# head-board.net
KiCad netlist of a schematic drawn in EAGLE
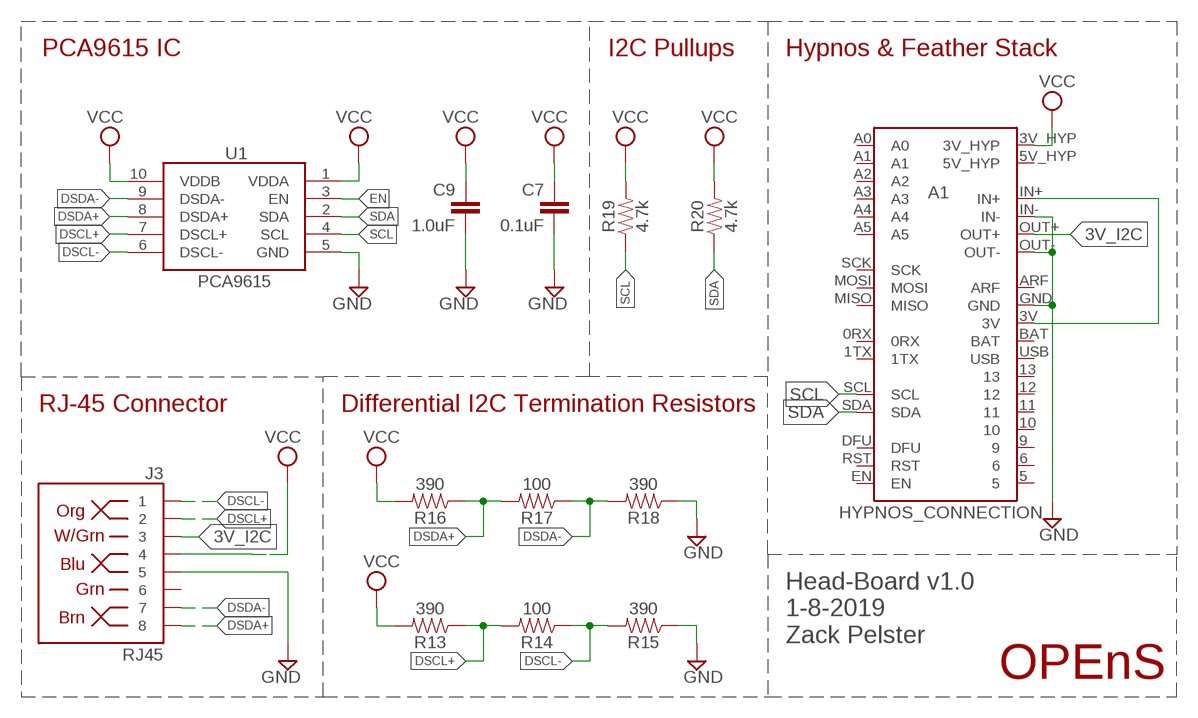
[diagram p0: schematic, sheet 1]

(export (version "E")
  (design (tool "Eeschema 10.0.6"))
  (components
    (comp (ref "A1")
      (value "HYPNOS_CONNECTION")
      (footprint "eagle-import:HYPNOS_CONNECTION")
      (libsource (lib "eagle-import") (part "HYPNOS_CONNECTION"))
    )
    (comp (ref "C7")
      (value "0.1uF")
      (footprint "eagle-import:0603")
      (libsource (lib "eagle-import") (part "0.1UF-0603-25V-(+80/-20%)"))
    )
    (comp (ref "C9")
      (value "1.0uF")
      (footprint "eagle-import:0603")
      (libsource (lib "eagle-import") (part "1.0UF-0603-16V-10%"))
    )
    (comp (ref "J3")
      (value "RJ45")
      (footprint "eagle-import:RJ45-8")
      (libsource (lib "eagle-import") (part "RJ45-8"))
    )
    (comp (ref "R13")
      (value "390")
      (footprint "eagle-import:0603")
      (libsource (lib "eagle-import") (part "390OHM-0603-1/10W-1%"))
    )
    (comp (ref "R14")
      (value "100")
      (footprint "eagle-import:0603")
      (libsource (lib "eagle-import") (part "100OHM-0603-1/10W-1%"))
    )
    (comp (ref "R15")
      (value "390")
      (footprint "eagle-import:0603")
      (libsource (lib "eagle-import") (part "390OHM-0603-1/10W-1%"))
    )
    (comp (ref "R16")
      (value "390")
      (footprint "eagle-import:0603")
      (libsource (lib "eagle-import") (part "390OHM-0603-1/10W-1%"))
    )
    (comp (ref "R17")
      (value "100")
      (footprint "eagle-import:0603")
      (libsource (lib "eagle-import") (part "100OHM-0603-1/10W-1%"))
    )
    (comp (ref "R18")
      (value "390")
      (footprint "eagle-import:0603")
      (libsource (lib "eagle-import") (part "390OHM-0603-1/10W-1%"))
    )
    (comp (ref "R19")
      (value "4.7k")
      (footprint "eagle-import:0603")
      (libsource (lib "eagle-import") (part "4.7KOHM-0603-1/10W-1%"))
    )
    (comp (ref "R20")
      (value "4.7k")
      (footprint "eagle-import:0603")
      (libsource (lib "eagle-import") (part "4.7KOHM-0603-1/10W-1%"))
    )
    (comp (ref "U$1")
      (value "OPENS-LOGO")
      (footprint "eagle-import:OPENS-LOGO")
      (libsource (lib "eagle-import") (part "OPENS-LOGO"))
    )
    (comp (ref "U1")
      (value "PCA9615")
      (footprint "eagle-import:TSSOP10")
      (libsource (lib "eagle-import") (part "PCA9615"))
    )
  )
  (nets
    (net (code "1") (name "/BAT") (class "Default")
      (node (ref "A1") (pin "BAT") (pinfunction "BAT_BAT") (pintype "power_in"))
    )
    (net (code "2") (name "/USB") (class "Default")
      (node (ref "A1") (pin "USB") (pinfunction "USB_USB") (pintype "power_in"))
    )
    (net (code "3") (name "3V_I2C") (class "Default")
      (node (ref "A1") (pin "OUT+") (pinfunction "OUT+_OUT+") (pintype "bidirectional"))
      (node (ref "J3") (pin "3") (pinfunction "3_3") (pintype "bidirectional"))
    )
    (net (code "4") (name "DSCL+") (class "Default")
      (node (ref "J3") (pin "2") (pinfunction "2_2") (pintype "bidirectional"))
      (node (ref "R13") (pin "1") (pinfunction "1_1") (pintype "passive"))
      (node (ref "R14") (pin "2") (pinfunction "2_2") (pintype "passive"))
      (node (ref "U1") (pin "7") (pinfunction "DSCL+_7") (pintype "bidirectional"))
    )
    (net (code "5") (name "DSCL-") (class "Default")
      (node (ref "J3") (pin "1") (pinfunction "1_1") (pintype "bidirectional"))
      (node (ref "R14") (pin "1") (pinfunction "1_1") (pintype "passive"))
      (node (ref "R15") (pin "2") (pinfunction "2_2") (pintype "passive"))
      (node (ref "U1") (pin "6") (pinfunction "DSCL-_6") (pintype "bidirectional"))
    )
    (net (code "6") (name "DSDA+") (class "Default")
      (node (ref "J3") (pin "8") (pinfunction "8_8") (pintype "bidirectional"))
      (node (ref "R16") (pin "1") (pinfunction "1_1") (pintype "passive"))
      (node (ref "R17") (pin "2") (pinfunction "2_2") (pintype "passive"))
      (node (ref "U1") (pin "8") (pinfunction "DSDA+_8") (pintype "bidirectional"))
    )
    (net (code "7") (name "DSDA-") (class "Default")
      (node (ref "J3") (pin "7") (pinfunction "7_7") (pintype "bidirectional"))
      (node (ref "R17") (pin "1") (pinfunction "1_1") (pintype "passive"))
      (node (ref "R18") (pin "2") (pinfunction "2_2") (pintype "passive"))
      (node (ref "U1") (pin "9") (pinfunction "DSDA-_9") (pintype "bidirectional"))
    )
    (net (code "8") (name "EN") (class "Default")
      (node (ref "U1") (pin "3") (pinfunction "EN_3") (pintype "bidirectional"))
    )
    (net (code "9") (name "GND") (class "Default")
      (node (ref "A1") (pin "GND") (pinfunction "GND_GND") (pintype "power_in"))
      (node (ref "A1") (pin "IN-") (pinfunction "IN-_IN-") (pintype "bidirectional"))
      (node (ref "A1") (pin "OUT-") (pinfunction "OUT-_OUT-") (pintype "bidirectional"))
      (node (ref "C7") (pin "2") (pinfunction "2_2") (pintype "passive"))
      (node (ref "C9") (pin "2") (pinfunction "2_2") (pintype "passive"))
      (node (ref "J3") (pin "5") (pinfunction "5_5") (pintype "bidirectional"))
      (node (ref "R15") (pin "1") (pinfunction "1_1") (pintype "passive"))
      (node (ref "R18") (pin "1") (pinfunction "1_1") (pintype "passive"))
      (node (ref "U1") (pin "5") (pinfunction "GND_5") (pintype "bidirectional"))
    )
    (net (code "10") (name "Net-(A1-Pad3V)") (class "Default")
      (node (ref "A1") (pin "3V") (pinfunction "3V_3V") (pintype "power_in"))
      (node (ref "A1") (pin "IN+") (pinfunction "IN+_IN+") (pintype "bidirectional"))
    )
    (net (code "11") (name "SCL") (class "Default")
      (node (ref "A1") (pin "SCL") (pinfunction "SCL_SCL") (pintype "bidirectional"))
      (node (ref "R19") (pin "1") (pinfunction "1_1") (pintype "passive"))
      (node (ref "U1") (pin "4") (pinfunction "SCL_4") (pintype "bidirectional"))
    )
    (net (code "12") (name "SDA") (class "Default")
      (node (ref "A1") (pin "SDA") (pinfunction "SDA_SDA") (pintype "bidirectional"))
      (node (ref "R20") (pin "1") (pinfunction "1_1") (pintype "passive"))
      (node (ref "U1") (pin "2") (pinfunction "SDA_2") (pintype "bidirectional"))
    )
    (net (code "13") (name "VCC") (class "Default")
      (node (ref "A1") (pin "3V_HYP") (pinfunction "3V_HYP_3V_HYP") (pintype "bidirectional"))
      (node (ref "C7") (pin "1") (pinfunction "1_1") (pintype "passive"))
      (node (ref "C9") (pin "1") (pinfunction "1_1") (pintype "passive"))
      (node (ref "J3") (pin "4") (pinfunction "4_4") (pintype "bidirectional"))
      (node (ref "R13") (pin "2") (pinfunction "2_2") (pintype "passive"))
      (node (ref "R16") (pin "2") (pinfunction "2_2") (pintype "passive"))
      (node (ref "R19") (pin "2") (pinfunction "2_2") (pintype "passive"))
      (node (ref "R20") (pin "2") (pinfunction "2_2") (pintype "passive"))
      (node (ref "U1") (pin "1") (pinfunction "VDDA_1") (pintype "bidirectional"))
      (node (ref "U1") (pin "10") (pinfunction "VDDB_10") (pintype "bidirectional"))
    )
    (net (code "14") (name "unconnected-(A1-Pad0RX)") (class "Default")
      (node (ref "A1") (pin "0RX") (pinfunction "0RX_0RX") (pintype "bidirectional"))
    )
    (net (code "15") (name "unconnected-(A1-Pad1TX)") (class "Default")
      (node (ref "A1") (pin "1TX") (pinfunction "1TX_1TX") (pintype "bidirectional"))
    )
    (net (code "16") (name "unconnected-(A1-Pad5)") (class "Default")
      (node (ref "A1") (pin "5") (pinfunction "5_5") (pintype "bidirectional"))
    )
    (net (code "17") (name "unconnected-(A1-Pad5V_HYP)") (class "Default")
      (node (ref "A1") (pin "5V_HYP") (pinfunction "5V_HYP_5V_HYP") (pintype "bidirectional"))
    )
    (net (code "18") (name "unconnected-(A1-Pad6)") (class "Default")
      (node (ref "A1") (pin "6") (pinfunction "6_6") (pintype "bidirectional"))
    )
    (net (code "19") (name "unconnected-(A1-Pad9)") (class "Default")
      (node (ref "A1") (pin "9") (pinfunction "9_9") (pintype "bidirectional"))
    )
    (net (code "20") (name "unconnected-(A1-Pad10)") (class "Default")
      (node (ref "A1") (pin "10") (pinfunction "10_10") (pintype "bidirectional"))
    )
    (net (code "21") (name "unconnected-(A1-Pad11)") (class "Default")
      (node (ref "A1") (pin "11") (pinfunction "11_11") (pintype "bidirectional"))
    )
    (net (code "22") (name "unconnected-(A1-Pad12)") (class "Default")
      (node (ref "A1") (pin "12") (pinfunction "12_12") (pintype "bidirectional"))
    )
    (net (code "23") (name "unconnected-(A1-Pad13)") (class "Default")
      (node (ref "A1") (pin "13") (pinfunction "13_13") (pintype "bidirectional"))
    )
    (net (code "24") (name "unconnected-(A1-PadA0)") (class "Default")
      (node (ref "A1") (pin "A0") (pinfunction "A0_A0") (pintype "bidirectional"))
    )
    (net (code "25") (name "unconnected-(A1-PadA1)") (class "Default")
      (node (ref "A1") (pin "A1") (pinfunction "A1_A1") (pintype "bidirectional"))
    )
    (net (code "26") (name "unconnected-(A1-PadA2)") (class "Default")
      (node (ref "A1") (pin "A2") (pinfunction "A2_A2") (pintype "bidirectional"))
    )
    (net (code "27") (name "unconnected-(A1-PadA3)") (class "Default")
      (node (ref "A1") (pin "A3") (pinfunction "A3_A3") (pintype "bidirectional"))
    )
    (net (code "28") (name "unconnected-(A1-PadA4)") (class "Default")
      (node (ref "A1") (pin "A4") (pinfunction "A4_A4") (pintype "bidirectional"))
    )
    (net (code "29") (name "unconnected-(A1-PadA5)") (class "Default")
      (node (ref "A1") (pin "A5") (pinfunction "A5_A5") (pintype "bidirectional"))
    )
    (net (code "30") (name "unconnected-(A1-PadARF)") (class "Default")
      (node (ref "A1") (pin "ARF") (pinfunction "ARF_ARF") (pintype "bidirectional"))
    )
    (net (code "31") (name "unconnected-(A1-PadDFU)") (class "Default")
      (node (ref "A1") (pin "DFU") (pinfunction "DFU_DFU") (pintype "bidirectional"))
    )
    (net (code "32") (name "unconnected-(A1-PadEN)") (class "Default")
      (node (ref "A1") (pin "EN") (pinfunction "EN_EN") (pintype "bidirectional"))
    )
    (net (code "33") (name "unconnected-(A1-PadMISO)") (class "Default")
      (node (ref "A1") (pin "MISO") (pinfunction "MISO_MISO") (pintype "bidirectional"))
    )
    (net (code "34") (name "unconnected-(A1-PadMOSI)") (class "Default")
      (node (ref "A1") (pin "MOSI") (pinfunction "MOSI_MOSI") (pintype "bidirectional"))
    )
    (net (code "35") (name "unconnected-(A1-PadRST)") (class "Default")
      (node (ref "A1") (pin "RST") (pinfunction "RST_RST") (pintype "bidirectional"))
    )
    (net (code "36") (name "unconnected-(A1-PadSCK)") (class "Default")
      (node (ref "A1") (pin "SCK") (pinfunction "SCK_SCK") (pintype "bidirectional"))
    )
    (net (code "37") (name "unconnected-(J3-Pad6)") (class "Default")
      (node (ref "J3") (pin "6") (pinfunction "6_6") (pintype "bidirectional"))
    )
  )
)
